# old_line_kick.net
KiCad netlist of a schematic drawn in EAGLE
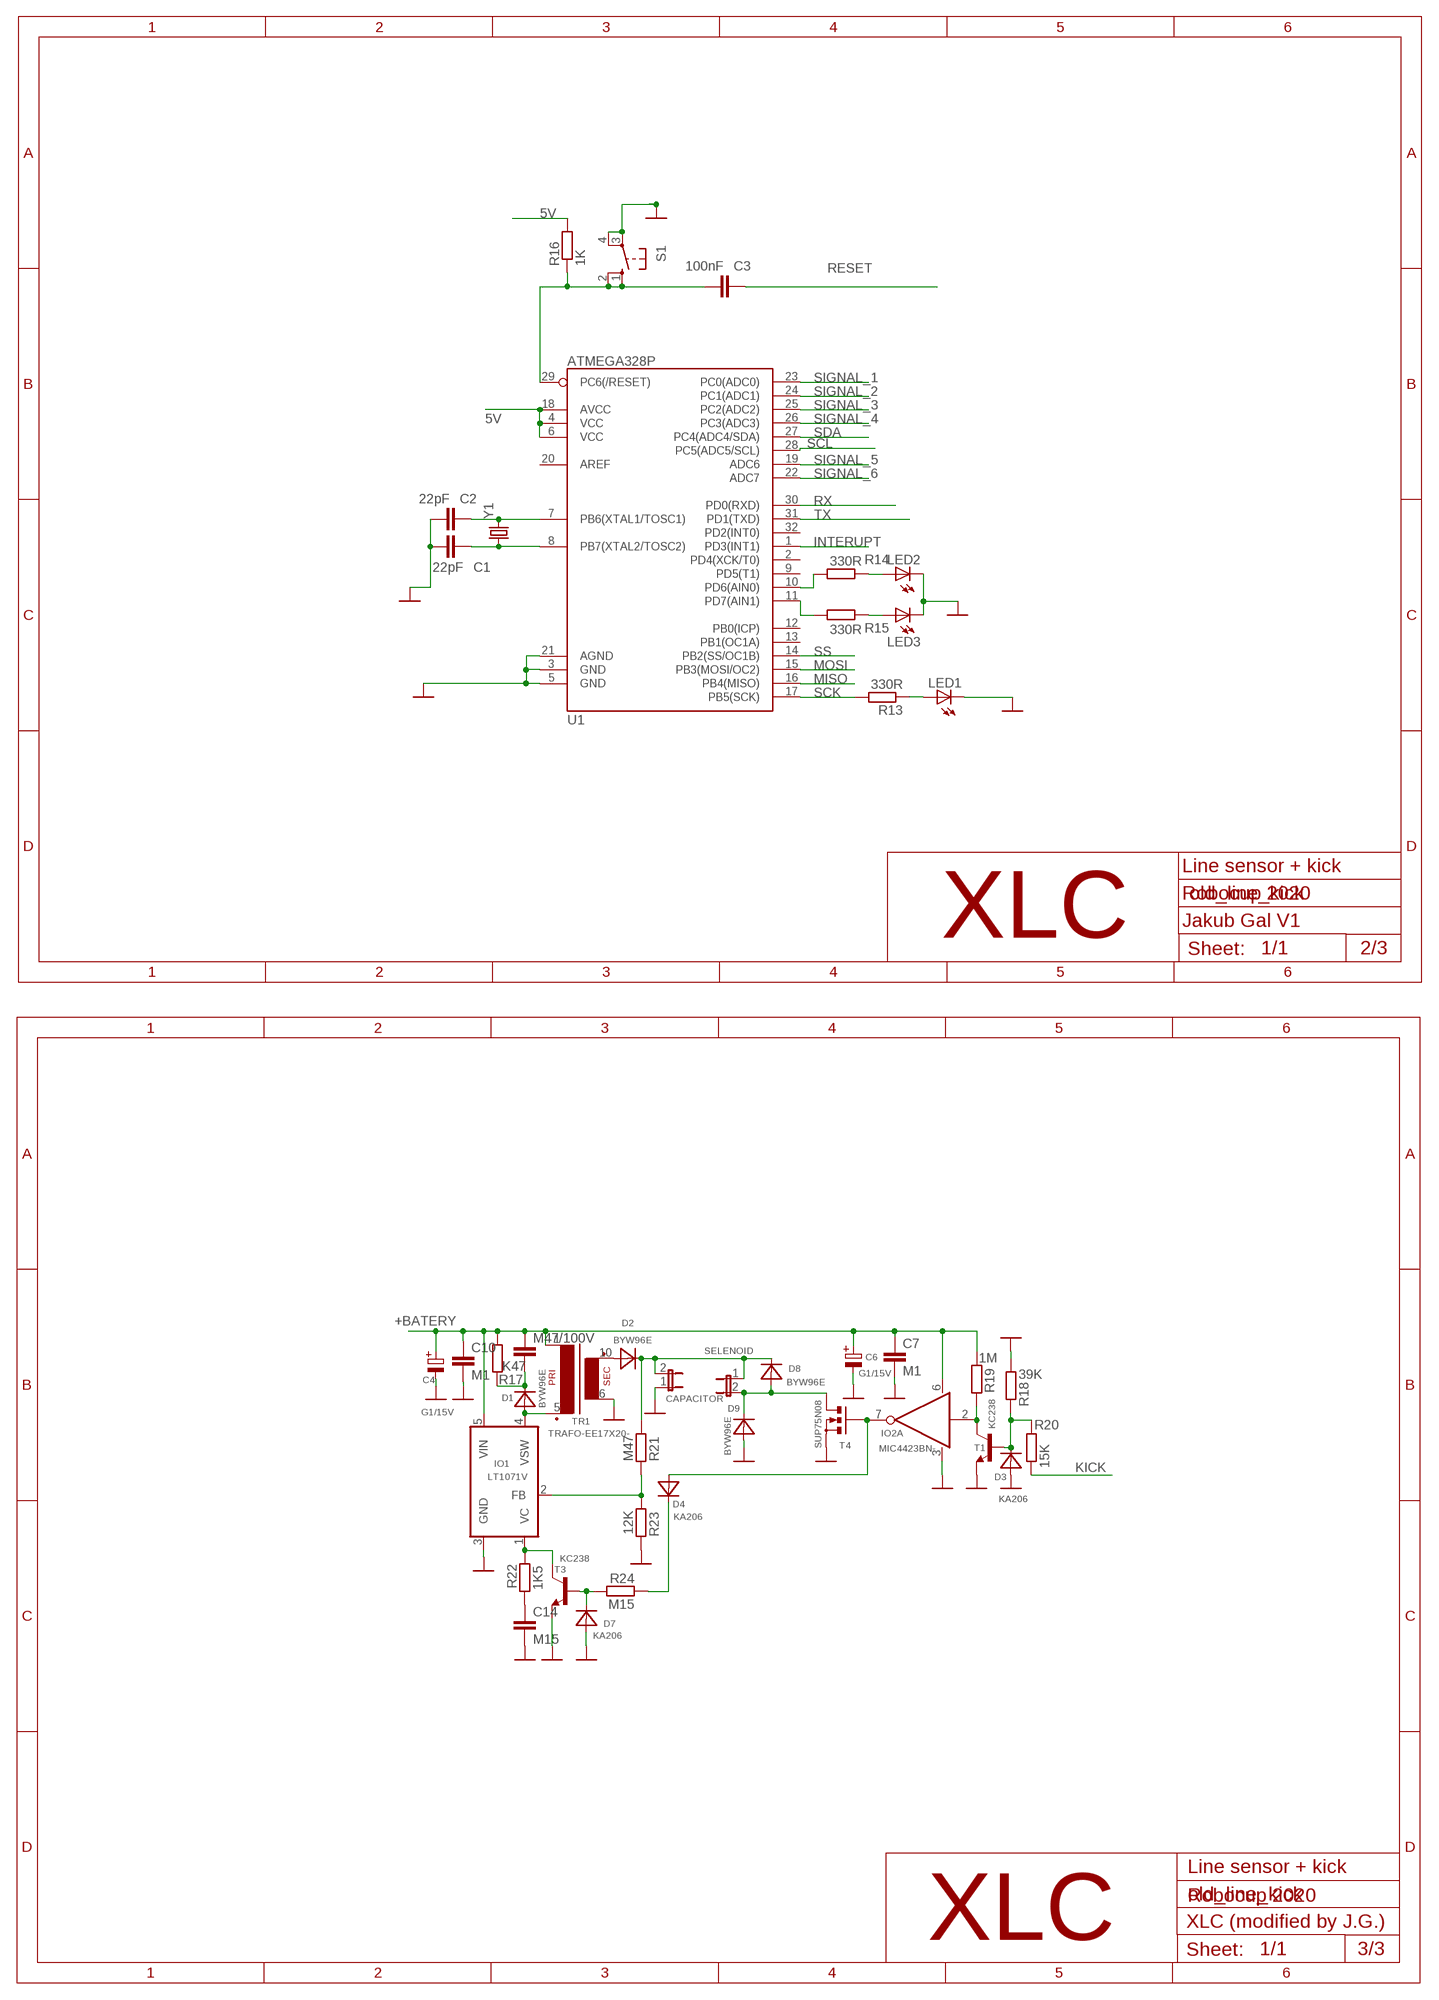
[diagram p0: schematic, sheet 1, part 1 of 2]
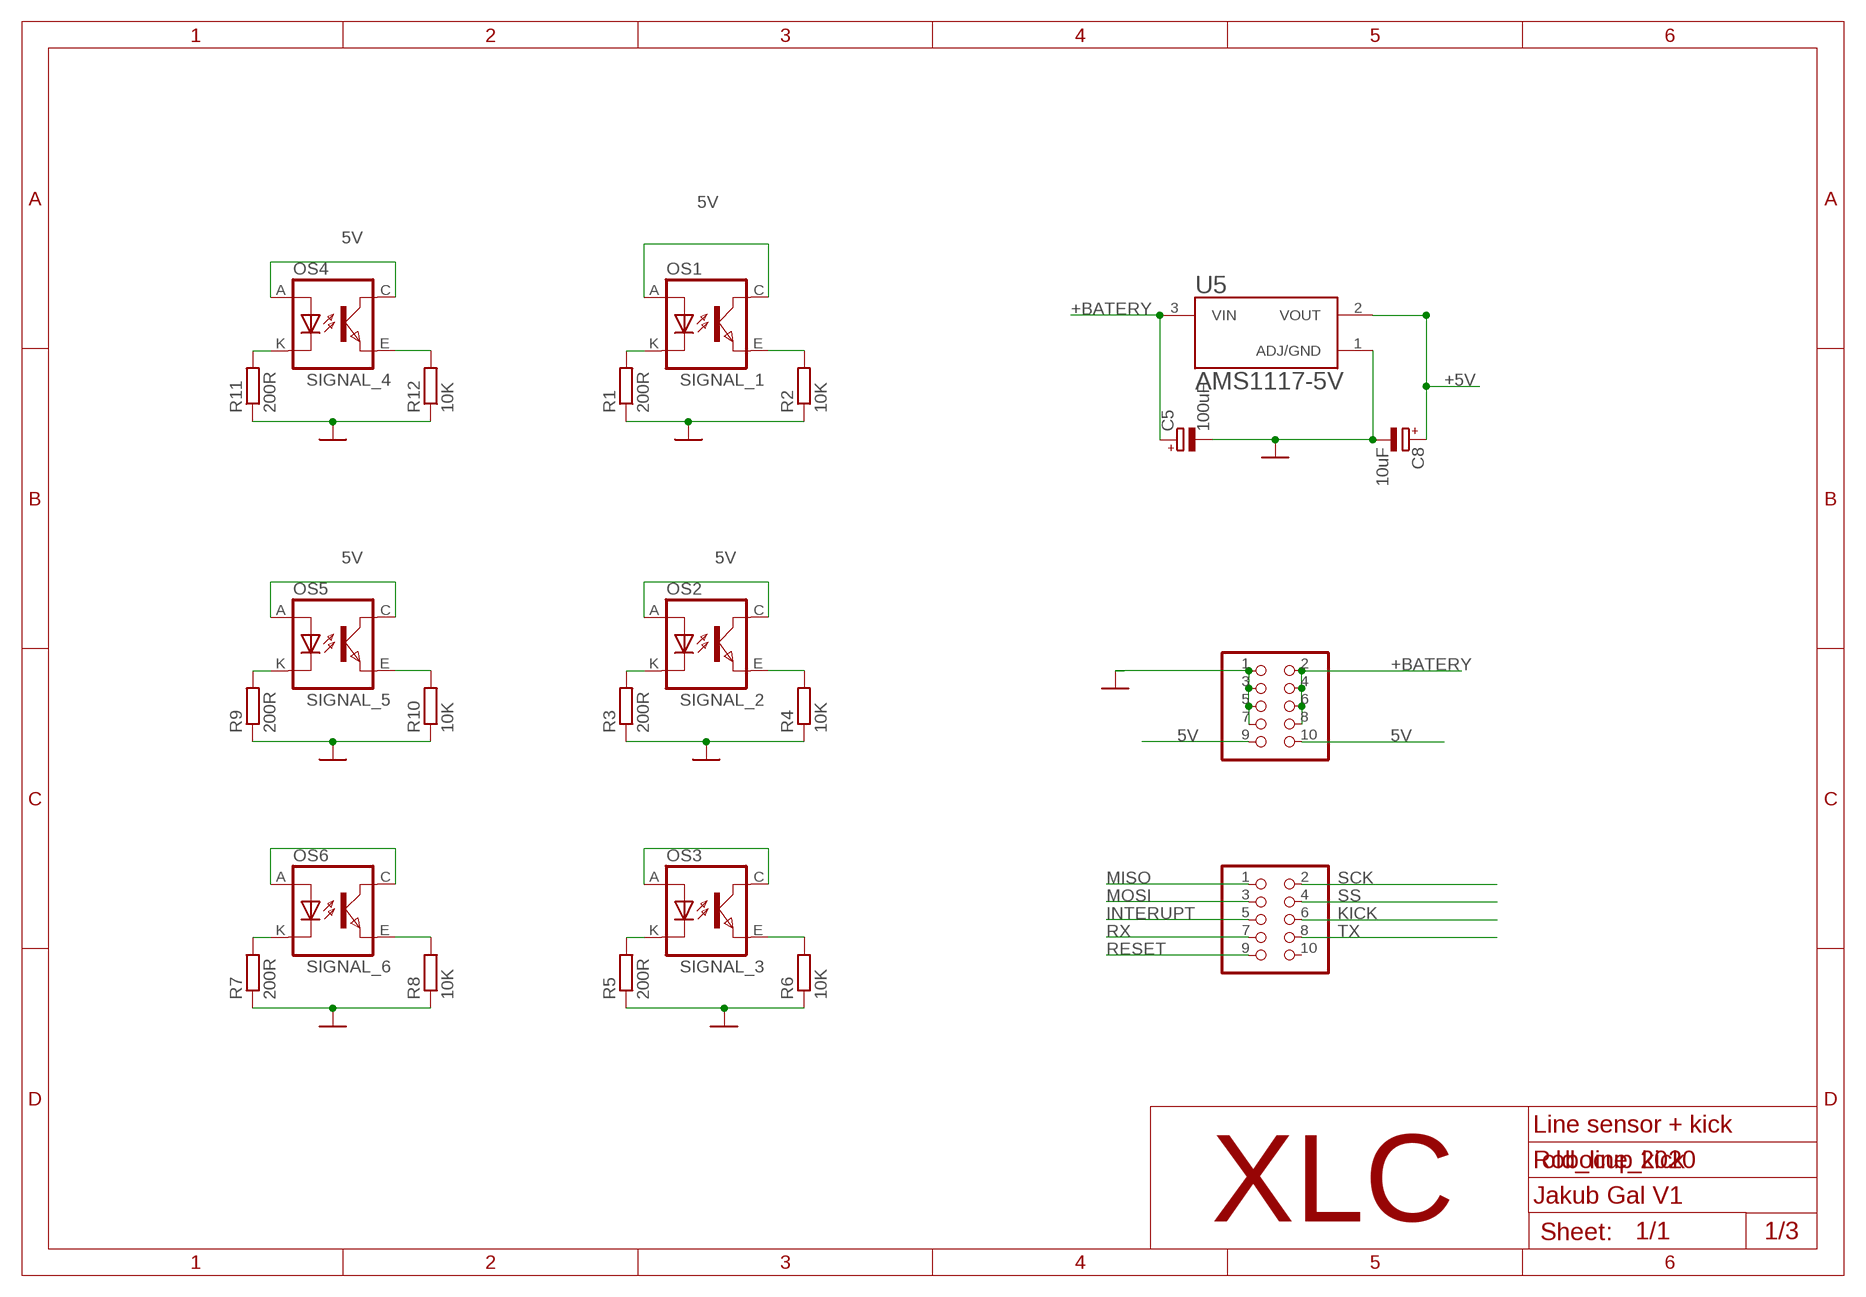
[diagram p1: schematic, sheet 1, part 2 of 2]

(export (version "E")
  (design (tool "Eeschema 10.0.6"))
  (components
    (comp (ref "C1")
      (value "22pF")
      (footprint "eagle-import:C0603")
      (libsource (lib "eagle-import") (part "C-EUC0603"))
    )
    (comp (ref "C2")
      (value "22pF")
      (footprint "eagle-import:C0603")
      (libsource (lib "eagle-import") (part "C-EUC0603"))
    )
    (comp (ref "C3")
      (value "100nF")
      (footprint "eagle-import:C0603")
      (libsource (lib "eagle-import") (part "C-EUC0603"))
    )
    (comp (ref "C4")
      (value "G1/15V")
      (footprint "eagle-import:E-2,5_7-RAD")
      (libsource (lib "eagle-import") (part "KOND-ELEKT-2,5/7"))
    )
    (comp (ref "C5")
      (value "100uF")
      (footprint "eagle-import:UD-6,3X7,7_NICHICON")
      (libsource (lib "eagle-import") (part "CPOL-EUUD-6,3X7,7"))
    )
    (comp (ref "C6")
      (value "G1/15V")
      (footprint "eagle-import:E-2,5_7-RAD")
      (libsource (lib "eagle-import") (part "KOND-ELEKT-2,5/7"))
    )
    (comp (ref "C7")
      (value "M1")
      (footprint "eagle-import:C0805K")
      (libsource (lib "eagle-import") (part "resistor_C-EUC0805K"))
    )
    (comp (ref "C8")
      (value "10uF")
      (footprint "eagle-import:UD-4X5,8_NICHICON")
      (libsource (lib "eagle-import") (part "CPOL-EUUD-4X5,8"))
    )
    (comp (ref "C10")
      (value "M1")
      (footprint "eagle-import:C0805K")
      (libsource (lib "eagle-import") (part "resistor_C-EUC0805K"))
    )
    (comp (ref "C14")
      (value "M15")
      (footprint "eagle-import:C0805K")
      (libsource (lib "eagle-import") (part "resistor_C-EUC0805K"))
    )
    (comp (ref "CAPACITOR")
      (value "JP2EN")
      (footprint "eagle-import:JP2E")
      (libsource (lib "eagle-import") (part "JP2EN"))
    )
    (comp (ref "D1")
      (value "BYW96E")
      (footprint "eagle-import:D-10")
      (libsource (lib "eagle-import") (part "DIODA-10MM"))
    )
    (comp (ref "D2")
      (value "BYW96E")
      (footprint "eagle-import:D-10")
      (libsource (lib "eagle-import") (part "DIODA-10MM"))
    )
    (comp (ref "D3")
      (value "KA206")
      (footprint "eagle-import:D-7,5")
      (libsource (lib "eagle-import") (part "DIODA-7,5MM"))
    )
    (comp (ref "D4")
      (value "KA206")
      (footprint "eagle-import:D-7,5")
      (libsource (lib "eagle-import") (part "DIODA-7,5MM"))
    )
    (comp (ref "D7")
      (value "KA206")
      (footprint "eagle-import:D-7,5")
      (libsource (lib "eagle-import") (part "DIODA-7,5MM"))
    )
    (comp (ref "D8")
      (value "BYW96E")
      (footprint "eagle-import:D-10")
      (libsource (lib "eagle-import") (part "DIODA-10MM"))
    )
    (comp (ref "D9")
      (value "BYW96E")
      (footprint "eagle-import:D-10")
      (libsource (lib "eagle-import") (part "DIODA-10MM"))
    )
    (comp (ref "IO1")
      (value "LT1071V")
      (footprint "eagle-import:TO-220-5P")
      (libsource (lib "eagle-import") (part "LT1071V"))
    )
    (comp (ref "IO2")
      (value "MIC4423BN-")
      (footprint "eagle-import:DIL8")
      (libsource (lib "eagle-import") (part "MIC4423BN-"))
    )
    (comp (ref "JP2")
      (value "PINHD-2X5")
      (footprint "eagle-import:2X05")
      (libsource (lib "eagle-import") (part "PINHD-2X5"))
    )
    (comp (ref "JP3")
      (value "PINHD-2X5")
      (footprint "eagle-import:2X05")
      (libsource (lib "eagle-import") (part "PINHD-2X5"))
    )
    (comp (ref "LED1")
      (value "LEDCHIPLED_0603")
      (footprint "eagle-import:CHIPLED_0603")
      (libsource (lib "eagle-import") (part "LEDCHIPLED_0603"))
    )
    (comp (ref "LED2")
      (value "LEDCHIPLED_0603")
      (footprint "eagle-import:CHIPLED_0603")
      (libsource (lib "eagle-import") (part "LEDCHIPLED_0603"))
    )
    (comp (ref "LED3")
      (value "LEDCHIPLED_0603")
      (footprint "eagle-import:CHIPLED_0603")
      (libsource (lib "eagle-import") (part "LEDCHIPLED_0603"))
    )
    (comp (ref "M47/100V")
      (value "C-EUC0805K")
      (footprint "eagle-import:C0805K")
      (libsource (lib "eagle-import") (part "resistor_C-EUC0805K"))
    )
    (comp (ref "OS1")
      (value "TCRT5000")
      (footprint "eagle-import:TCRT5000")
      (libsource (lib "eagle-import") (part "TCRT5000"))
    )
    (comp (ref "OS2")
      (value "TCRT5000")
      (footprint "eagle-import:TCRT5000")
      (libsource (lib "eagle-import") (part "TCRT5000"))
    )
    (comp (ref "OS3")
      (value "TCRT5000")
      (footprint "eagle-import:TCRT5000")
      (libsource (lib "eagle-import") (part "TCRT5000"))
    )
    (comp (ref "OS4")
      (value "TCRT5000")
      (footprint "eagle-import:TCRT5000")
      (fields (field (name "SPICEPREFIX") "O"))
      (libsource (lib "eagle-import") (part "TCRT5000"))
    )
    (comp (ref "OS5")
      (value "TCRT5000")
      (footprint "eagle-import:TCRT5000")
      (libsource (lib "eagle-import") (part "TCRT5000"))
    )
    (comp (ref "OS6")
      (value "TCRT5000")
      (footprint "eagle-import:TCRT5000")
      (fields (field (name "SPICEPREFIX") "O"))
      (libsource (lib "eagle-import") (part "TCRT5000"))
    )
    (comp (ref "R1")
      (value "200R")
      (footprint "eagle-import:R0603")
      (libsource (lib "eagle-import") (part "R-EU_R0603"))
    )
    (comp (ref "R2")
      (value "10K")
      (footprint "eagle-import:R0603")
      (libsource (lib "eagle-import") (part "R-EU_R0603"))
    )
    (comp (ref "R3")
      (value "200R")
      (footprint "eagle-import:R0603")
      (libsource (lib "eagle-import") (part "R-EU_R0603"))
    )
    (comp (ref "R4")
      (value "10K")
      (footprint "eagle-import:R0603")
      (libsource (lib "eagle-import") (part "R-EU_R0603"))
    )
    (comp (ref "R5")
      (value "200R")
      (footprint "eagle-import:R0603")
      (libsource (lib "eagle-import") (part "R-EU_R0603"))
    )
    (comp (ref "R6")
      (value "10K")
      (footprint "eagle-import:R0603")
      (libsource (lib "eagle-import") (part "R-EU_R0603"))
    )
    (comp (ref "R7")
      (value "200R")
      (footprint "eagle-import:R0603")
      (libsource (lib "eagle-import") (part "R-EU_R0603"))
    )
    (comp (ref "R8")
      (value "10K")
      (footprint "eagle-import:R0603")
      (libsource (lib "eagle-import") (part "R-EU_R0603"))
    )
    (comp (ref "R9")
      (value "200R")
      (footprint "eagle-import:R0603")
      (libsource (lib "eagle-import") (part "R-EU_R0603"))
    )
    (comp (ref "R10")
      (value "10K")
      (footprint "eagle-import:R0603")
      (libsource (lib "eagle-import") (part "R-EU_R0603"))
    )
    (comp (ref "R11")
      (value "200R")
      (footprint "eagle-import:R0603")
      (libsource (lib "eagle-import") (part "R-EU_R0603"))
    )
    (comp (ref "R12")
      (value "10K")
      (footprint "eagle-import:R0603")
      (libsource (lib "eagle-import") (part "R-EU_R0603"))
    )
    (comp (ref "R13")
      (value "330R")
      (footprint "eagle-import:R0603")
      (libsource (lib "eagle-import") (part "R-EU_R0603"))
    )
    (comp (ref "R14")
      (value "330R")
      (footprint "eagle-import:R0603")
      (libsource (lib "eagle-import") (part "R-EU_R0603"))
    )
    (comp (ref "R15")
      (value "330R")
      (footprint "eagle-import:R0603")
      (libsource (lib "eagle-import") (part "R-EU_R0603"))
    )
    (comp (ref "R16")
      (value "1K")
      (footprint "eagle-import:R0603")
      (libsource (lib "eagle-import") (part "R-EU_R0603"))
    )
    (comp (ref "R17")
      (value "K47")
      (footprint "eagle-import:R0603")
      (libsource (lib "eagle-import") (part "resistor_R-EU_R0603"))
    )
    (comp (ref "R18")
      (value "39K")
      (footprint "eagle-import:R0603")
      (libsource (lib "eagle-import") (part "resistor_R-EU_R0603"))
    )
    (comp (ref "R19")
      (value "1M")
      (footprint "eagle-import:R0603")
      (libsource (lib "eagle-import") (part "resistor_R-EU_R0603"))
    )
    (comp (ref "R20")
      (value "15K")
      (footprint "eagle-import:R0603")
      (libsource (lib "eagle-import") (part "resistor_R-EU_R0603"))
    )
    (comp (ref "R21")
      (value "M47")
      (footprint "eagle-import:R0603")
      (libsource (lib "eagle-import") (part "resistor_R-EU_R0603"))
    )
    (comp (ref "R22")
      (value "1K5")
      (footprint "eagle-import:R0603")
      (libsource (lib "eagle-import") (part "resistor_R-EU_R0603"))
    )
    (comp (ref "R23")
      (value "12K")
      (footprint "eagle-import:R0603")
      (libsource (lib "eagle-import") (part "resistor_R-EU_R0603"))
    )
    (comp (ref "R24")
      (value "M15")
      (footprint "eagle-import:R0603")
      (libsource (lib "eagle-import") (part "resistor_R-EU_R0603"))
    )
    (comp (ref "S1")
      (value "10-XX")
      (footprint "eagle-import:B3F-10XX")
      (fields (field (name "MPN") "B3F-1000"))
      (libsource (lib "eagle-import") (part "10-XX"))
    )
    (comp (ref "SELENOID")
      (value "JP2EN")
      (footprint "eagle-import:JP2E")
      (libsource (lib "eagle-import") (part "JP2EN"))
    )
    (comp (ref "T1")
      (value "KC238")
      (footprint "eagle-import:TO-92")
      (libsource (lib "eagle-import") (part "TRANZ-NPN-KC238-PLAST"))
    )
    (comp (ref "T3")
      (value "KC238")
      (footprint "eagle-import:TO-92")
      (libsource (lib "eagle-import") (part "TRANZ-NPN-KC238-PLAST"))
    )
    (comp (ref "T4")
      (value "SUP75N08")
      (footprint "eagle-import:TO-220")
      (libsource (lib "eagle-import") (part "BUZ90{dblquote}"))
    )
    (comp (ref "TR1")
      (value "TRAFO-EE17X20-")
      (footprint "eagle-import:TRAFO-EE17X20")
      (libsource (lib "eagle-import") (part "TRAFO-EE17X20-"))
    )
    (comp (ref "U1")
      (value "ATMEGA328P")
      (footprint "eagle-import:TQFP32-08")
      (libsource (lib "eagle-import") (part "ATMEGA328_SMT"))
    )
    (comp (ref "U5")
      (value "AMS1117-5V")
      (footprint "eagle-import:SOT229P700X180-4N")
      (fields (field (name "MF") "Advanced Monolithic Systems") (field (name "MP") "AMS1117-3.3"))
      (libsource (lib "eagle-import") (part "AMS1117-3.3"))
    )
    (comp (ref "Y1")
      (value "CRYSTALHC49US")
      (footprint "eagle-import:HC49US")
      (libsource (lib "eagle-import") (part "CRYSTALHC49US"))
    )
  )
  (nets
    (net (code "1") (name "/+5V") (class "Default")
      (node (ref "C8") (pin "+") (pinfunction "+_+") (pintype "passive"))
      (node (ref "U5") (pin "2") (pinfunction "VOUT_2") (pintype "output"))
    )
    (net (code "2") (name "/+BATERY") (class "Default")
      (node (ref "C10") (pin "1") (pinfunction "1_1") (pintype "passive"))
      (node (ref "C4") (pin "+") (pinfunction "+_+") (pintype "passive"))
      (node (ref "C5") (pin "+") (pinfunction "+_+") (pintype "passive"))
      (node (ref "C6") (pin "+") (pinfunction "+_+") (pintype "passive"))
      (node (ref "C7") (pin "1") (pinfunction "1_1") (pintype "passive"))
      (node (ref "IO1") (pin "5") (pinfunction "VIN_5") (pintype "power_in"))
      (node (ref "IO2") (pin "6") (pinfunction "VCC_6") (pintype "power_in"))
      (node (ref "JP3") (pin "2") (pinfunction "2_2") (pintype "passive"))
      (node (ref "JP3") (pin "4") (pinfunction "4_4") (pintype "passive"))
      (node (ref "JP3") (pin "6") (pinfunction "6_6") (pintype "passive"))
      (node (ref "JP3") (pin "8") (pinfunction "8_8") (pintype "passive"))
      (node (ref "M47/100V") (pin "1") (pinfunction "1_1") (pintype "passive"))
      (node (ref "R17") (pin "1") (pinfunction "1_1") (pintype "passive"))
      (node (ref "R19") (pin "2") (pinfunction "2_2") (pintype "passive"))
      (node (ref "TR1") (pin "1") (pinfunction "1_1") (pintype "passive"))
      (node (ref "U5") (pin "3") (pinfunction "VIN_3") (pintype "input"))
    )
    (net (code "3") (name "/5V") (class "Default")
      (node (ref "JP3") (pin "10") (pinfunction "10_10") (pintype "passive"))
      (node (ref "JP3") (pin "9") (pinfunction "9_9") (pintype "passive"))
      (node (ref "OS1") (pin "A") (pinfunction "ANODE_A") (pintype "passive"))
      (node (ref "OS1") (pin "C") (pinfunction "COLLECTOR_C") (pintype "passive"))
      (node (ref "OS2") (pin "A") (pinfunction "ANODE_A") (pintype "passive"))
      (node (ref "OS2") (pin "C") (pinfunction "COLLECTOR_C") (pintype "passive"))
      (node (ref "OS3") (pin "A") (pinfunction "ANODE_A") (pintype "passive"))
      (node (ref "OS3") (pin "C") (pinfunction "COLLECTOR_C") (pintype "passive"))
      (node (ref "OS4") (pin "A") (pinfunction "ANODE_A") (pintype "passive"))
      (node (ref "OS4") (pin "C") (pinfunction "COLLECTOR_C") (pintype "passive"))
      (node (ref "OS5") (pin "A") (pinfunction "ANODE_A") (pintype "passive"))
      (node (ref "OS5") (pin "C") (pinfunction "COLLECTOR_C") (pintype "passive"))
      (node (ref "OS6") (pin "A") (pinfunction "ANODE_A") (pintype "passive"))
      (node (ref "OS6") (pin "C") (pinfunction "COLLECTOR_C") (pintype "passive"))
      (node (ref "R16") (pin "2") (pinfunction "2_2") (pintype "passive"))
      (node (ref "U1") (pin "18") (pinfunction "AVCC_18") (pintype "bidirectional"))
      (node (ref "U1") (pin "4") (pinfunction "VCC_4") (pintype "bidirectional"))
      (node (ref "U1") (pin "6") (pinfunction "VCC_6") (pintype "bidirectional"))
    )
    (net (code "4") (name "/INTERUPT") (class "Default")
      (node (ref "JP2") (pin "5") (pinfunction "5_5") (pintype "passive"))
      (node (ref "U1") (pin "1") (pinfunction "PD3(INT1)_1") (pintype "bidirectional"))
    )
    (net (code "5") (name "/KICK") (class "Default")
      (node (ref "JP2") (pin "6") (pinfunction "6_6") (pintype "passive"))
      (node (ref "R20") (pin "1") (pinfunction "1_1") (pintype "passive"))
    )
    (net (code "6") (name "/MISO") (class "Default")
      (node (ref "JP2") (pin "1") (pinfunction "1_1") (pintype "passive"))
      (node (ref "U1") (pin "16") (pinfunction "PB4(MISO)_16") (pintype "bidirectional"))
    )
    (net (code "7") (name "/MOSI") (class "Default")
      (node (ref "JP2") (pin "3") (pinfunction "3_3") (pintype "passive"))
      (node (ref "U1") (pin "15") (pinfunction "PB3(MOSI/OC2)_15") (pintype "bidirectional"))
    )
    (net (code "8") (name "/RESET") (class "Default")
      (node (ref "C3") (pin "2") (pinfunction "2_2") (pintype "passive"))
      (node (ref "JP2") (pin "9") (pinfunction "9_9") (pintype "passive"))
    )
    (net (code "9") (name "/RX") (class "Default")
      (node (ref "JP2") (pin "7") (pinfunction "7_7") (pintype "passive"))
      (node (ref "U1") (pin "30") (pinfunction "PD0(RXD)_30") (pintype "bidirectional"))
    )
    (net (code "10") (name "/SCK") (class "Default")
      (node (ref "JP2") (pin "2") (pinfunction "2_2") (pintype "passive"))
      (node (ref "R13") (pin "2") (pinfunction "2_2") (pintype "passive"))
      (node (ref "U1") (pin "17") (pinfunction "PB5(SCK)_17") (pintype "bidirectional"))
    )
    (net (code "11") (name "/SCL") (class "Default")
      (node (ref "U1") (pin "28") (pinfunction "PC5(ADC5/SCL)_28") (pintype "bidirectional"))
    )
    (net (code "12") (name "/SDA") (class "Default")
      (node (ref "U1") (pin "27") (pinfunction "PC4(ADC4/SDA)_27") (pintype "bidirectional"))
    )
    (net (code "13") (name "/SIGNAL_1") (class "Default")
      (node (ref "OS1") (pin "E") (pinfunction "EMITTER_E") (pintype "passive"))
      (node (ref "R2") (pin "2") (pinfunction "2_2") (pintype "passive"))
      (node (ref "U1") (pin "23") (pinfunction "PC0(ADC0)_23") (pintype "bidirectional"))
    )
    (net (code "14") (name "/SIGNAL_2") (class "Default")
      (node (ref "OS2") (pin "E") (pinfunction "EMITTER_E") (pintype "passive"))
      (node (ref "R4") (pin "2") (pinfunction "2_2") (pintype "passive"))
      (node (ref "U1") (pin "24") (pinfunction "PC1(ADC1)_24") (pintype "bidirectional"))
    )
    (net (code "15") (name "/SIGNAL_3") (class "Default")
      (node (ref "OS3") (pin "E") (pinfunction "EMITTER_E") (pintype "passive"))
      (node (ref "R6") (pin "2") (pinfunction "2_2") (pintype "passive"))
      (node (ref "U1") (pin "25") (pinfunction "PC2(ADC2)_25") (pintype "bidirectional"))
    )
    (net (code "16") (name "/SIGNAL_4") (class "Default")
      (node (ref "OS4") (pin "E") (pinfunction "EMITTER_E") (pintype "passive"))
      (node (ref "R12") (pin "2") (pinfunction "2_2") (pintype "passive"))
      (node (ref "U1") (pin "26") (pinfunction "PC3(ADC3)_26") (pintype "bidirectional"))
    )
    (net (code "17") (name "/SIGNAL_5") (class "Default")
      (node (ref "OS5") (pin "E") (pinfunction "EMITTER_E") (pintype "passive"))
      (node (ref "R10") (pin "2") (pinfunction "2_2") (pintype "passive"))
      (node (ref "U1") (pin "19") (pinfunction "ADC6_19") (pintype "bidirectional"))
    )
    (net (code "18") (name "/SIGNAL_6") (class "Default")
      (node (ref "OS6") (pin "E") (pinfunction "EMITTER_E") (pintype "passive"))
      (node (ref "R8") (pin "2") (pinfunction "2_2") (pintype "passive"))
      (node (ref "U1") (pin "22") (pinfunction "ADC7_22") (pintype "bidirectional"))
    )
    (net (code "19") (name "/SS") (class "Default")
      (node (ref "JP2") (pin "4") (pinfunction "4_4") (pintype "passive"))
      (node (ref "U1") (pin "14") (pinfunction "PB2(SS/OC1B)_14") (pintype "bidirectional"))
    )
    (net (code "20") (name "/TX") (class "Default")
      (node (ref "JP2") (pin "8") (pinfunction "8_8") (pintype "passive"))
      (node (ref "U1") (pin "31") (pinfunction "PD1(TXD)_31") (pintype "bidirectional"))
    )
    (net (code "21") (name "GND") (class "Default")
      (node (ref "C1") (pin "1") (pinfunction "1_1") (pintype "passive"))
      (node (ref "C10") (pin "2") (pinfunction "2_2") (pintype "passive"))
      (node (ref "C14") (pin "2") (pinfunction "2_2") (pintype "passive"))
      (node (ref "C2") (pin "1") (pinfunction "1_1") (pintype "passive"))
      (node (ref "C4") (pin "-") (pinfunction "-_-") (pintype "passive"))
      (node (ref "C5") (pin "-") (pinfunction "-_-") (pintype "passive"))
      (node (ref "C6") (pin "-") (pinfunction "-_-") (pintype "passive"))
      (node (ref "C7") (pin "2") (pinfunction "2_2") (pintype "passive"))
      (node (ref "C8") (pin "-") (pinfunction "-_-") (pintype "passive"))
      (node (ref "CAPACITOR") (pin "1") (pinfunction "1_1") (pintype "passive"))
      (node (ref "D3") (pin "A") (pinfunction "A_A") (pintype "passive"))
      (node (ref "D7") (pin "A") (pinfunction "A_A") (pintype "passive"))
      (node (ref "D9") (pin "A") (pinfunction "A_A") (pintype "passive"))
      (node (ref "IO1") (pin "3") (pinfunction "GND_3") (pintype "power_in"))
      (node (ref "IO2") (pin "3") (pinfunction "GND_3") (pintype "power_in"))
      (node (ref "JP3") (pin "1") (pinfunction "1_1") (pintype "passive"))
      (node (ref "JP3") (pin "3") (pinfunction "3_3") (pintype "passive"))
      (node (ref "JP3") (pin "5") (pinfunction "5_5") (pintype "passive"))
      (node (ref "JP3") (pin "7") (pinfunction "7_7") (pintype "passive"))
      (node (ref "LED1") (pin "C") (pinfunction "C_C") (pintype "passive"))
      (node (ref "LED2") (pin "C") (pinfunction "C_C") (pintype "passive"))
      (node (ref "LED3") (pin "C") (pinfunction "C_C") (pintype "passive"))
      (node (ref "R1") (pin "1") (pinfunction "1_1") (pintype "passive"))
      (node (ref "R10") (pin "1") (pinfunction "1_1") (pintype "passive"))
      (node (ref "R11") (pin "1") (pinfunction "1_1") (pintype "passive"))
      (node (ref "R12") (pin "1") (pinfunction "1_1") (pintype "passive"))
      (node (ref "R18") (pin "2") (pinfunction "2_2") (pintype "passive"))
      (node (ref "R2") (pin "1") (pinfunction "1_1") (pintype "passive"))
      (node (ref "R23") (pin "1") (pinfunction "1_1") (pintype "passive"))
      (node (ref "R3") (pin "1") (pinfunction "1_1") (pintype "passive"))
      (node (ref "R4") (pin "1") (pinfunction "1_1") (pintype "passive"))
      (node (ref "R5") (pin "1") (pinfunction "1_1") (pintype "passive"))
      (node (ref "R6") (pin "1") (pinfunction "1_1") (pintype "passive"))
      (node (ref "R7") (pin "1") (pinfunction "1_1") (pintype "passive"))
      (node (ref "R8") (pin "1") (pinfunction "1_1") (pintype "passive"))
      (node (ref "R9") (pin "1") (pinfunction "1_1") (pintype "passive"))
      (node (ref "S1") (pin "3") (pinfunction "P_3") (pintype "passive"))
      (node (ref "S1") (pin "4") (pinfunction "P1_4") (pintype "passive"))
      (node (ref "T1") (pin "3") (pinfunction "E_3") (pintype "passive"))
      (node (ref "T3") (pin "3") (pinfunction "E_3") (pintype "passive"))
      (node (ref "T4") (pin "3") (pinfunction "S_3") (pintype "passive"))
      (node (ref "TR1") (pin "6") (pinfunction "3_6") (pintype "passive"))
      (node (ref "U1") (pin "21") (pinfunction "AGND_21") (pintype "bidirectional"))
      (node (ref "U1") (pin "3") (pinfunction "GND_3") (pintype "bidirectional"))
      (node (ref "U1") (pin "5") (pinfunction "GND_5") (pintype "bidirectional"))
      (node (ref "U5") (pin "1") (pinfunction "ADJ/GND_1") (pintype "power_in"))
    )
    (net (code "22") (name "Net-(C14-Pad1)") (class "Default")
      (node (ref "C14") (pin "1") (pinfunction "1_1") (pintype "passive"))
      (node (ref "R22") (pin "2") (pinfunction "2_2") (pintype "passive"))
    )
    (net (code "23") (name "Net-(CAPACITOR-Pad2)") (class "Default")
      (node (ref "CAPACITOR") (pin "2") (pinfunction "2_2") (pintype "passive"))
      (node (ref "D2") (pin "K") (pinfunction "K_K") (pintype "passive"))
      (node (ref "D8") (pin "K") (pinfunction "K_K") (pintype "passive"))
      (node (ref "R21") (pin "2") (pinfunction "2_2") (pintype "passive"))
      (node (ref "SELENOID") (pin "1") (pinfunction "1_1") (pintype "passive"))
    )
    (net (code "24") (name "Net-(D1-PadK)") (class "Default")
      (node (ref "D1") (pin "K") (pinfunction "K_K") (pintype "passive"))
      (node (ref "M47/100V") (pin "2") (pinfunction "2_2") (pintype "passive"))
      (node (ref "R17") (pin "2") (pinfunction "2_2") (pintype "passive"))
    )
    (net (code "25") (name "Net-(D4-PadK)") (class "Default")
      (node (ref "D4") (pin "K") (pinfunction "K_K") (pintype "passive"))
      (node (ref "R24") (pin "1") (pinfunction "1_1") (pintype "passive"))
    )
    (net (code "26") (name "Net-(IO1-FB)") (class "Default")
      (node (ref "IO1") (pin "2") (pinfunction "FB_2") (pintype "input"))
      (node (ref "R21") (pin "1") (pinfunction "1_1") (pintype "passive"))
      (node (ref "R23") (pin "2") (pinfunction "2_2") (pintype "passive"))
    )
    (net (code "27") (name "Net-(IO1-VC)") (class "Default")
      (node (ref "IO1") (pin "1") (pinfunction "VC_1") (pintype "input"))
      (node (ref "R22") (pin "1") (pinfunction "1_1") (pintype "passive"))
      (node (ref "T3") (pin "1") (pinfunction "C_1") (pintype "passive"))
    )
    (net (code "28") (name "Net-(IO1-VSW)") (class "Default")
      (node (ref "D1") (pin "A") (pinfunction "A_A") (pintype "passive"))
      (node (ref "IO1") (pin "4") (pinfunction "VSW_4") (pintype "output"))
      (node (ref "TR1") (pin "5") (pinfunction "2_5") (pintype "passive"))
    )
    (net (code "29") (name "Net-(IO2A-I)") (class "Default")
      (node (ref "IO2") (pin "2") (pinfunction "I_2") (pintype "input"))
      (node (ref "R19") (pin "1") (pinfunction "1_1") (pintype "passive"))
      (node (ref "T1") (pin "1") (pinfunction "C_1") (pintype "passive"))
    )
    (net (code "30") (name "Net-(IO2A-O)") (class "Default")
      (node (ref "D4") (pin "A") (pinfunction "A_A") (pintype "passive"))
      (node (ref "IO2") (pin "7") (pinfunction "O_7") (pintype "output"))
      (node (ref "T4") (pin "1") (pinfunction "G_1") (pintype "passive"))
    )
    (net (code "31") (name "Net-(LED1-PadA)") (class "Default")
      (node (ref "LED1") (pin "A") (pinfunction "A_A") (pintype "passive"))
      (node (ref "R13") (pin "1") (pinfunction "1_1") (pintype "passive"))
    )
    (net (code "32") (name "Net-(LED2-PadA)") (class "Default")
      (node (ref "LED2") (pin "A") (pinfunction "A_A") (pintype "passive"))
      (node (ref "R14") (pin "1") (pinfunction "1_1") (pintype "passive"))
    )
    (net (code "33") (name "Net-(LED3-PadA)") (class "Default")
      (node (ref "LED3") (pin "A") (pinfunction "A_A") (pintype "passive"))
      (node (ref "R15") (pin "1") (pinfunction "1_1") (pintype "passive"))
    )
    (net (code "34") (name "Net-(OS1-CATHODE)") (class "Default")
      (node (ref "OS1") (pin "K") (pinfunction "CATHODE_K") (pintype "passive"))
      (node (ref "R1") (pin "2") (pinfunction "2_2") (pintype "passive"))
    )
    (net (code "35") (name "Net-(OS2-CATHODE)") (class "Default")
      (node (ref "OS2") (pin "K") (pinfunction "CATHODE_K") (pintype "passive"))
      (node (ref "R3") (pin "2") (pinfunction "2_2") (pintype "passive"))
    )
    (net (code "36") (name "Net-(OS3-CATHODE)") (class "Default")
      (node (ref "OS3") (pin "K") (pinfunction "CATHODE_K") (pintype "passive"))
      (node (ref "R5") (pin "2") (pinfunction "2_2") (pintype "passive"))
    )
    (net (code "37") (name "Net-(OS4-CATHODE)") (class "Default")
      (node (ref "OS4") (pin "K") (pinfunction "CATHODE_K") (pintype "passive"))
      (node (ref "R11") (pin "2") (pinfunction "2_2") (pintype "passive"))
    )
    (net (code "38") (name "Net-(OS5-CATHODE)") (class "Default")
      (node (ref "OS5") (pin "K") (pinfunction "CATHODE_K") (pintype "passive"))
      (node (ref "R9") (pin "2") (pinfunction "2_2") (pintype "passive"))
    )
    (net (code "39") (name "Net-(OS6-CATHODE)") (class "Default")
      (node (ref "OS6") (pin "K") (pinfunction "CATHODE_K") (pintype "passive"))
      (node (ref "R7") (pin "2") (pinfunction "2_2") (pintype "passive"))
    )
    (net (code "40") (name "Net-(S1-S)") (class "Default")
      (node (ref "C3") (pin "1") (pinfunction "1_1") (pintype "passive"))
      (node (ref "R16") (pin "1") (pinfunction "1_1") (pintype "passive"))
      (node (ref "S1") (pin "1") (pinfunction "S_1") (pintype "passive"))
      (node (ref "S1") (pin "2") (pinfunction "S1_2") (pintype "passive"))
      (node (ref "U1") (pin "29") (pinfunction "PC6(/RESET)_29") (pintype "bidirectional"))
    )
    (net (code "41") (name "Net-(T1-B)") (class "Default")
      (node (ref "D3") (pin "K") (pinfunction "K_K") (pintype "passive"))
      (node (ref "R18") (pin "1") (pinfunction "1_1") (pintype "passive"))
      (node (ref "R20") (pin "2") (pinfunction "2_2") (pintype "passive"))
      (node (ref "T1") (pin "2") (pinfunction "B_2") (pintype "passive"))
    )
    (net (code "42") (name "Net-(T3-B)") (class "Default")
      (node (ref "D7") (pin "K") (pinfunction "K_K") (pintype "passive"))
      (node (ref "R24") (pin "2") (pinfunction "2_2") (pintype "passive"))
      (node (ref "T3") (pin "2") (pinfunction "B_2") (pintype "passive"))
    )
    (net (code "43") (name "Net-(T4-D)") (class "Default")
      (node (ref "D8") (pin "A") (pinfunction "A_A") (pintype "passive"))
      (node (ref "D9") (pin "K") (pinfunction "K_K") (pintype "passive"))
      (node (ref "SELENOID") (pin "2") (pinfunction "2_2") (pintype "passive"))
      (node (ref "T4") (pin "2") (pinfunction "D_2") (pintype "passive"))
    )
    (net (code "44") (name "Net-(TR1-4)") (class "Default")
      (node (ref "D2") (pin "A") (pinfunction "A_A") (pintype "passive"))
      (node (ref "TR1") (pin "10") (pinfunction "4_10") (pintype "passive"))
    )
    (net (code "45") (name "Net-(U1-PB6(XTAL1{slash}TOSC1))") (class "Default")
      (node (ref "C2") (pin "2") (pinfunction "2_2") (pintype "passive"))
      (node (ref "U1") (pin "7") (pinfunction "PB6(XTAL1/TOSC1)_7") (pintype "bidirectional"))
      (node (ref "Y1") (pin "2") (pinfunction "2_2") (pintype "passive"))
    )
    (net (code "46") (name "Net-(U1-PB7(XTAL2{slash}TOSC2))") (class "Default")
      (node (ref "C1") (pin "2") (pinfunction "2_2") (pintype "passive"))
      (node (ref "U1") (pin "8") (pinfunction "PB7(XTAL2/TOSC2)_8") (pintype "bidirectional"))
      (node (ref "Y1") (pin "1") (pinfunction "1_1") (pintype "passive"))
    )
    (net (code "47") (name "Net-(U1-PD6(AIN0))") (class "Default")
      (node (ref "R14") (pin "2") (pinfunction "2_2") (pintype "passive"))
      (node (ref "U1") (pin "10") (pinfunction "PD6(AIN0)_10") (pintype "bidirectional"))
    )
    (net (code "48") (name "Net-(U1-PD7(AIN1))") (class "Default")
      (node (ref "R15") (pin "2") (pinfunction "2_2") (pintype "passive"))
      (node (ref "U1") (pin "11") (pinfunction "PD7(AIN1)_11") (pintype "bidirectional"))
    )
    (net (code "49") (name "unconnected-(JP2-Pad10)") (class "Default")
      (node (ref "JP2") (pin "10") (pinfunction "10_10") (pintype "passive"))
    )
    (net (code "50") (name "unconnected-(U1-AREF-Pad20)") (class "Default")
      (node (ref "U1") (pin "20") (pinfunction "AREF_20") (pintype "bidirectional"))
    )
    (net (code "51") (name "unconnected-(U1-PB0(ICP)-Pad12)") (class "Default")
      (node (ref "U1") (pin "12") (pinfunction "PB0(ICP)_12") (pintype "bidirectional"))
    )
    (net (code "52") (name "unconnected-(U1-PB1(OC1A)-Pad13)") (class "Default")
      (node (ref "U1") (pin "13") (pinfunction "PB1(OC1A)_13") (pintype "bidirectional"))
    )
    (net (code "53") (name "unconnected-(U1-PD2(INT0)-Pad32)") (class "Default")
      (node (ref "U1") (pin "32") (pinfunction "PD2(INT0)_32") (pintype "bidirectional"))
    )
    (net (code "54") (name "unconnected-(U1-PD4(XCK{slash}T0)-Pad2)") (class "Default")
      (node (ref "U1") (pin "2") (pinfunction "PD4(XCK/T0)_2") (pintype "bidirectional"))
    )
    (net (code "55") (name "unconnected-(U1-PD5(T1)-Pad9)") (class "Default")
      (node (ref "U1") (pin "9") (pinfunction "PD5(T1)_9") (pintype "bidirectional"))
    )
  )
)
